# DCDC_Hall.net
KiCad netlist of a schematic drawn in Altium Designer
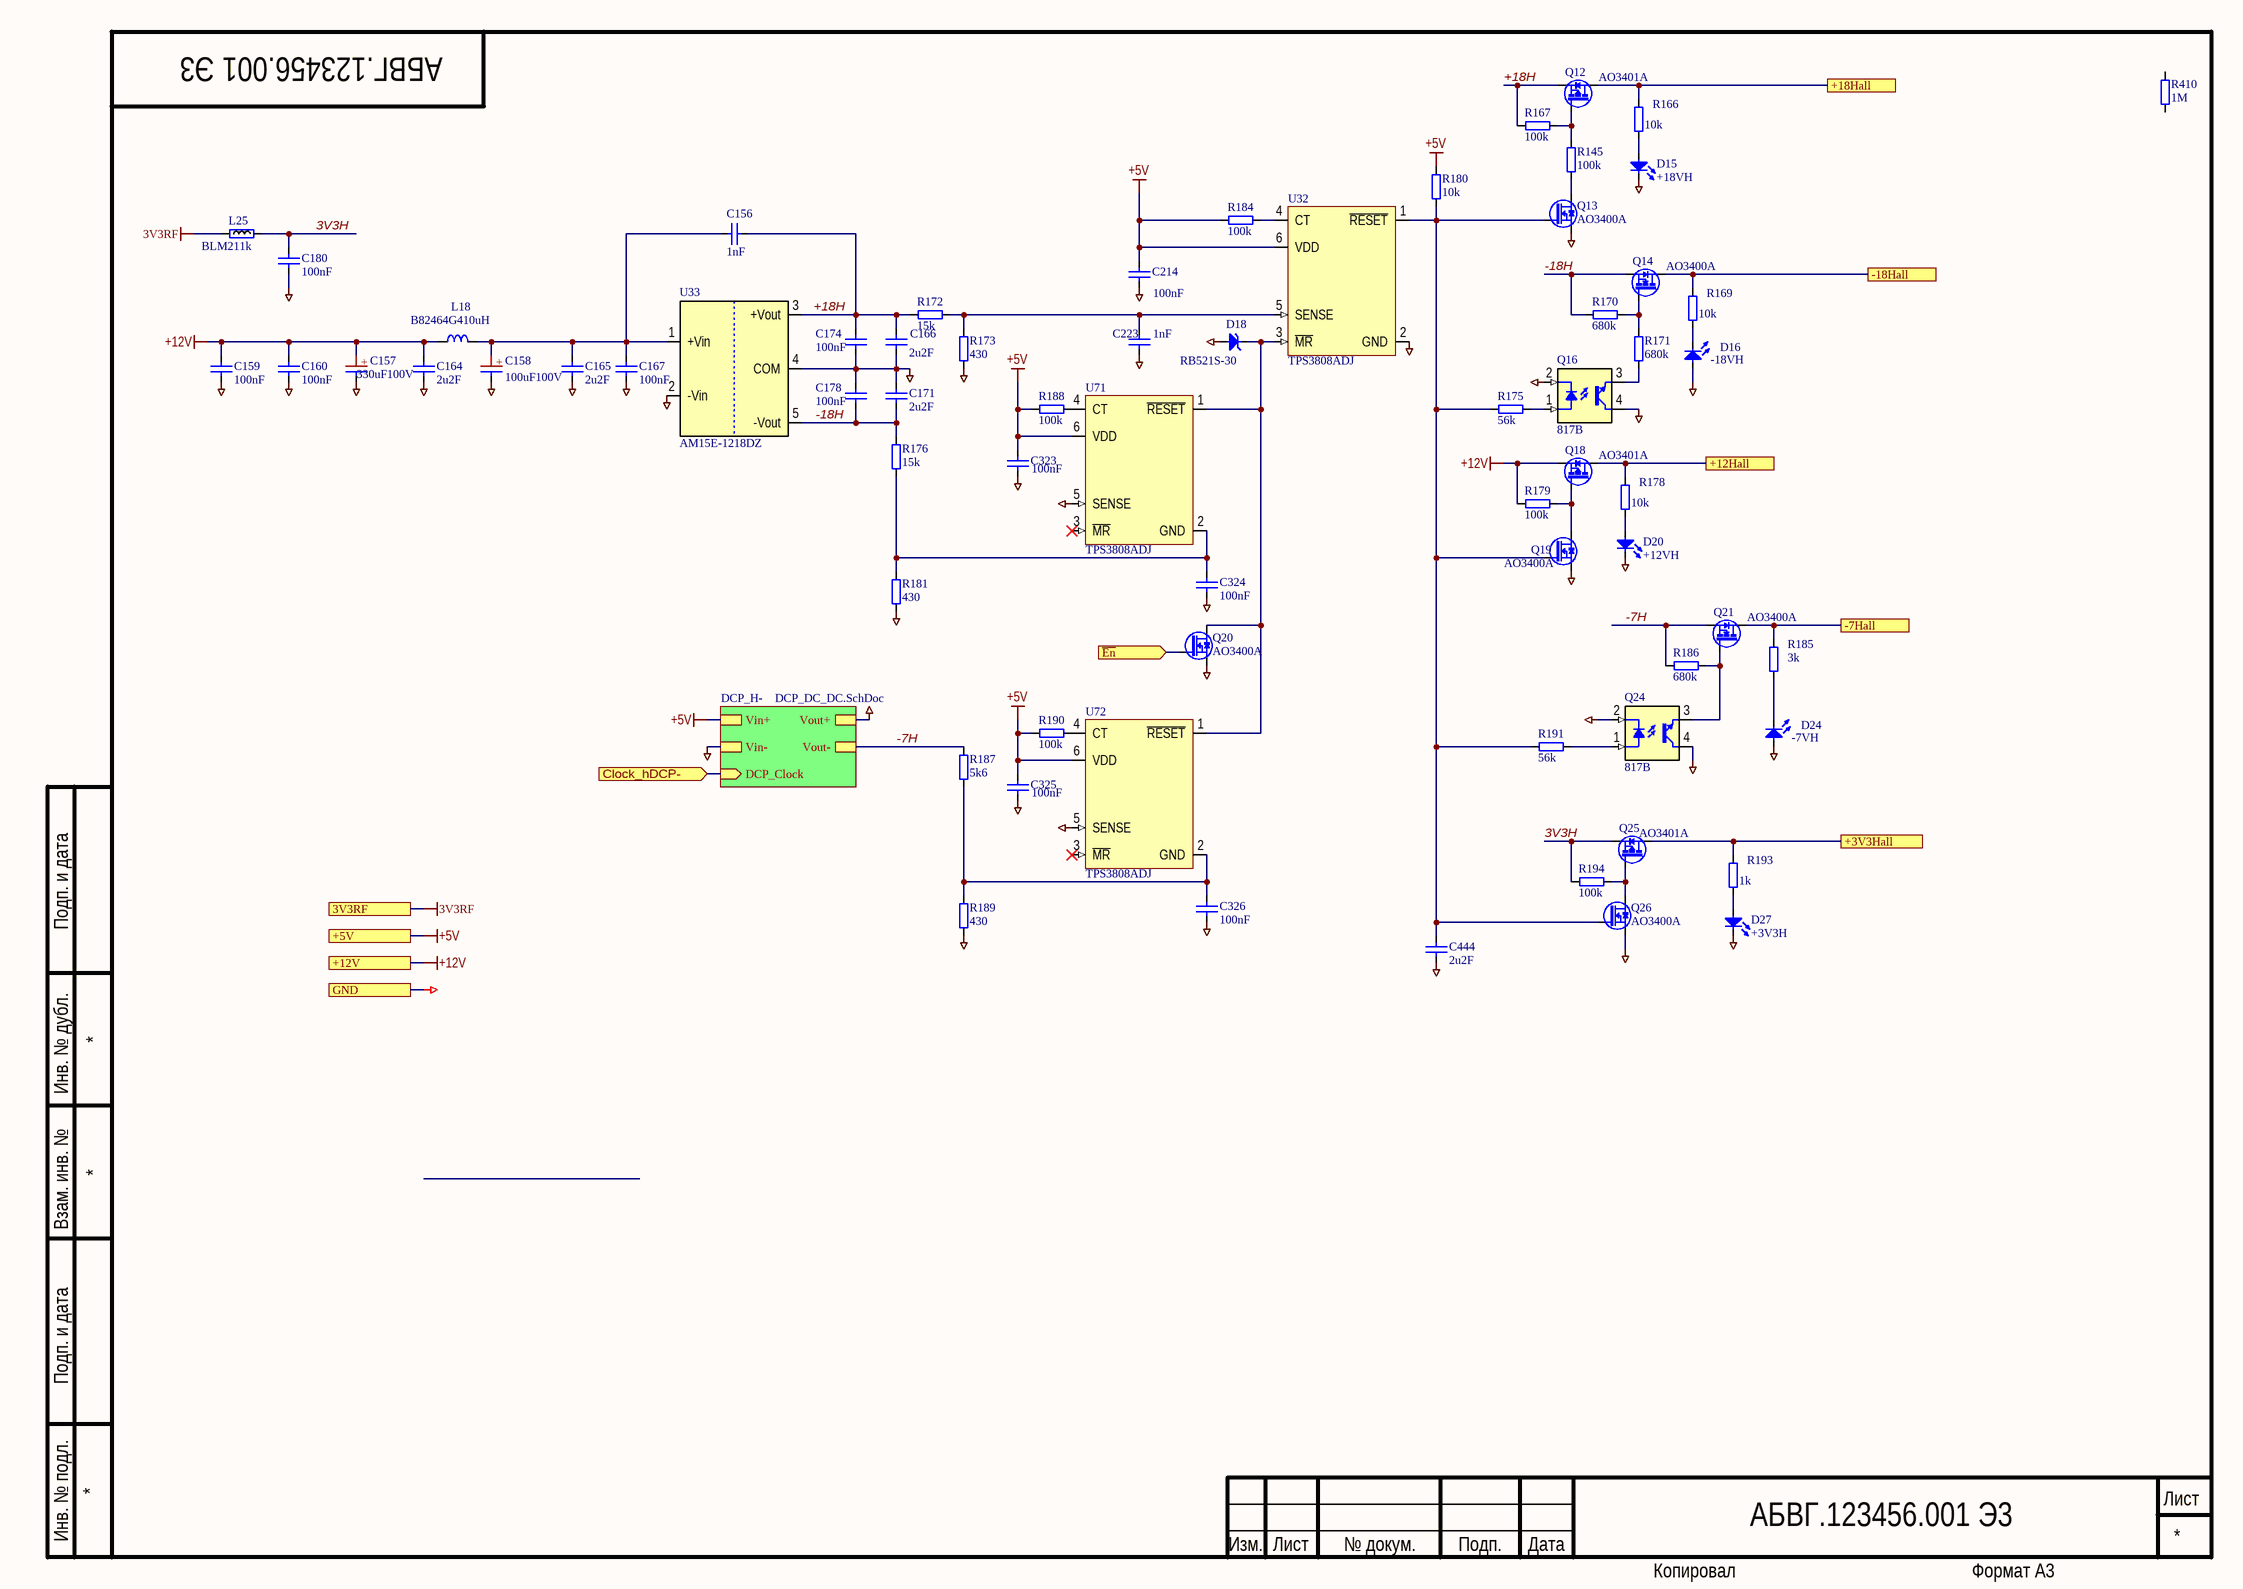
[diagram p0: DCDC_Hall.SchDoc]

(export (version "E")
  (design (tool "Eeschema 10.0.6"))
  (components
    (comp (ref "C156")
      (value "1nF")
      (footprint "SMD0805CAP")
      (description "Чип конденсатор 0805")
      (fields (field (name "VOLTAGE") "25V") (field (name "TOLERANCE") "20%"))
      (libsource (lib "DDSintLib") (part "C0805"))
    )
    (comp (ref "C157")
      (value "330uF100V")
      (footprint "CAPPR750-1600X2000")
      (description "Конденсатор полярный d16 p7.5мм")
      (fields (field (name "VOLTAGE") "100V") (field (name "TOLERANCE") "20%"))
      (libsource (lib "DDSintLib") (part "CAP_POL_7_5x16"))
    )
    (comp (ref "C158")
      (value "100uF100V")
      (footprint "CAPPR500-1000X1250")
      (description "Конденсатор полярный d10 p5мм")
      (fields (field (name "VOLTAGE") "100V") (field (name "TOLERANCE") "20%"))
      (libsource (lib "DDS1") (part "CAP_POL_5x10"))
    )
    (comp (ref "C159")
      (value "100nF")
      (footprint "SMD0805CAP")
      (description "Чип конденсатор 0805")
      (fields (field (name "VOLTAGE") "25V") (field (name "TOLERANCE") "20%"))
      (libsource (lib "DDSintLib") (part "C0805"))
    )
    (comp (ref "C160")
      (value "100nF")
      (footprint "SMD0805CAP")
      (description "Чип конденсатор 0805")
      (fields (field (name "VOLTAGE") "25V") (field (name "TOLERANCE") "20%"))
      (libsource (lib "DDSintLib") (part "C0805"))
    )
    (comp (ref "C164")
      (value "2u2F")
      (footprint "SMD0805CAP")
      (description "Чип конденсатор 0805")
      (fields (field (name "VOLTAGE") "25V") (field (name "TOLERANCE") "20%"))
      (libsource (lib "DDSintLib") (part "C0805"))
    )
    (comp (ref "C165")
      (value "2u2F")
      (footprint "SMD0805CAP")
      (description "Чип конденсатор 0805")
      (fields (field (name "VOLTAGE") "25V") (field (name "TOLERANCE") "20%"))
      (libsource (lib "DDSintLib") (part "C0805"))
    )
    (comp (ref "C166")
      (value "2u2F")
      (footprint "SMD0805CAP")
      (description "Чип конденсатор 0805")
      (fields (field (name "VOLTAGE") "25V") (field (name "TOLERANCE") "20%"))
      (libsource (lib "DDSintLib") (part "C0805"))
    )
    (comp (ref "C167")
      (value "100nF")
      (footprint "SMD0805CAP")
      (description "Чип конденсатор 0805")
      (fields (field (name "VOLTAGE") "25V") (field (name "TOLERANCE") "20%"))
      (libsource (lib "DDSintLib") (part "C0805"))
    )
    (comp (ref "C171")
      (value "2u2F")
      (footprint "SMD0805CAP")
      (description "Чип конденсатор 0805")
      (fields (field (name "VOLTAGE") "25V") (field (name "TOLERANCE") "20%"))
      (libsource (lib "DDSintLib") (part "C0805"))
    )
    (comp (ref "C174")
      (value "100nF")
      (footprint "SMD0805CAP")
      (description "Чип конденсатор 0805")
      (fields (field (name "VOLTAGE") "25V") (field (name "TOLERANCE") "20%"))
      (libsource (lib "DDSintLib") (part "C0805"))
    )
    (comp (ref "C178")
      (value "100nF")
      (footprint "SMD0805CAP")
      (description "Чип конденсатор 0805")
      (fields (field (name "VOLTAGE") "25V") (field (name "TOLERANCE") "20%"))
      (libsource (lib "DDSintLib") (part "C0805"))
    )
    (comp (ref "C180")
      (value "100nF")
      (footprint "SMD0805CAP")
      (description "Чип конденсатор 0805")
      (fields (field (name "VOLTAGE") "25V") (field (name "TOLERANCE") "20%"))
      (libsource (lib "DDSintLib") (part "C0805"))
    )
    (comp (ref "C214")
      (value "100nF")
      (footprint "SMD0805CAP")
      (description "Чип конденсатор 0805")
      (fields (field (name "VOLTAGE") "25V") (field (name "TOLERANCE") "20%"))
      (libsource (lib "DDSintLib") (part "C0805"))
    )
    (comp (ref "C223")
      (value "1nF")
      (footprint "SMD0805CAP")
      (description "Чип конденсатор 0805")
      (fields (field (name "VOLTAGE") "25V") (field (name "TOLERANCE") "20%"))
      (libsource (lib "DDSintLib") (part "C0805"))
    )
    (comp (ref "C323")
      (value "100nF")
      (footprint "SMD0805CAP")
      (description "Чип конденсатор 0805")
      (fields (field (name "VOLTAGE") "25V") (field (name "TOLERANCE") "20%"))
      (libsource (lib "DDSintLib") (part "C0805"))
    )
    (comp (ref "C324")
      (value "100nF")
      (footprint "SMD0805CAP")
      (description "Чип конденсатор 0805")
      (fields (field (name "VOLTAGE") "25V") (field (name "TOLERANCE") "20%"))
      (libsource (lib "DDSintLib") (part "C0805"))
    )
    (comp (ref "C325")
      (value "100nF")
      (footprint "SMD0805CAP")
      (description "Чип конденсатор 0805")
      (fields (field (name "VOLTAGE") "25V") (field (name "TOLERANCE") "20%"))
      (libsource (lib "DDSintLib") (part "C0805"))
    )
    (comp (ref "C326")
      (value "100nF")
      (footprint "SMD0805CAP")
      (description "Чип конденсатор 0805")
      (fields (field (name "VOLTAGE") "25V") (field (name "TOLERANCE") "20%"))
      (libsource (lib "DDSintLib") (part "C0805"))
    )
    (comp (ref "C444")
      (value "2u2F")
      (footprint "SMD0805CAP")
      (description "Чип конденсатор 0805")
      (fields (field (name "VOLTAGE") "25V") (field (name "TOLERANCE") "20%"))
      (libsource (lib "DDSintLib") (part "C0805"))
    )
    (comp (ref "D15")
      (value "+18VH")
      (footprint "LED0603")
      (description "Чип светодиод 0603")
      (libsource (lib "DDSintLib") (part "LED0603"))
    )
    (comp (ref "D16")
      (value "-18VH")
      (footprint "LED0603")
      (description "Чип светодиод 0603")
      (libsource (lib "DDSintLib") (part "LED0603"))
    )
    (comp (ref "D18")
      (value "RB521S-30")
      (footprint "SODFL1608X65N")
      (description "Чип Шоттки диод")
      (fields (field (name "VOLTAGE") "30V"))
      (libsource (lib "DDSintLib") (part "RB521S-30"))
    )
    (comp (ref "D20")
      (value "+12VH")
      (footprint "LED0603")
      (description "Чип светодиод 0603")
      (libsource (lib "DDSintLib") (part "LED0603"))
    )
    (comp (ref "D24")
      (value "-7VH")
      (footprint "LED0603")
      (description "Чип светодиод 0603")
      (libsource (lib "DDSintLib") (part "LED0603"))
    )
    (comp (ref "D27")
      (value "+3V3H")
      (footprint "LED0603")
      (description "Чип светодиод 0603")
      (libsource (lib "DDSintLib") (part "LED0603"))
    )
    (comp (ref "L18")
      (value "B82464G410uH")
      (footprint "IND_COILCRAFT_MSS1038")
      (description "SMD Дроссель")
      (fields (field (name "VOLTAGE") "2") (field (name "TOLERANCE") "20%"))
      (libsource (lib "DDSintLib") (part "B82464G4"))
    )
    (comp (ref "L25")
      (value "BLM211k")
      (footprint "RESC2012X50N")
      (description "SMD Ferrite bead 0805")
      (libsource (lib "DDSintLib") (part "BLM21"))
    )
    (comp (ref "Q12")
      (value "AO3401A")
      (footprint "SOT95P229X119-3N")
      (description "PMOS")
      (fields (field (name "VOLTAGE") "-30V"))
      (libsource (lib "DDSintLib") (part "AO3401A"))
    )
    (comp (ref "Q13")
      (value "AO3400A")
      (footprint "SOT95P229X119-3N")
      (description "NMOS")
      (fields (field (name "VOLTAGE") "30V"))
      (libsource (lib "DDSintLib") (part "AO3400A"))
    )
    (comp (ref "Q14")
      (value "AO3400A")
      (footprint "SOT95P229X119-3N")
      (description "NMOS")
      (fields (field (name "VOLTAGE") "30V"))
      (libsource (lib "DDSintLib") (part "AO3400A"))
    )
    (comp (ref "Q16")
      (value "817B")
      (footprint "DIP4-300")
      (description "Optotransistor")
      (fields (field (name "VOLTAGE") "35V"))
      (libsource (lib "DDS1") (part "817B"))
    )
    (comp (ref "Q18")
      (value "AO3401A")
      (footprint "SOT95P229X119-3N")
      (description "PMOS")
      (fields (field (name "VOLTAGE") "-30V"))
      (libsource (lib "DDSintLib") (part "AO3401A"))
    )
    (comp (ref "Q19")
      (value "AO3400A")
      (footprint "SOT95P229X119-3N")
      (description "NMOS")
      (fields (field (name "VOLTAGE") "30V"))
      (libsource (lib "DDSintLib") (part "AO3400A"))
    )
    (comp (ref "Q20")
      (value "AO3400A")
      (footprint "SOT95P229X119-3N")
      (description "NMOS")
      (fields (field (name "VOLTAGE") "30V"))
      (libsource (lib "DDSintLib") (part "AO3400A"))
    )
    (comp (ref "Q21")
      (value "AO3400A")
      (footprint "SOT95P229X119-3N")
      (description "NMOS")
      (fields (field (name "VOLTAGE") "30V"))
      (libsource (lib "DDSintLib") (part "AO3400A"))
    )
    (comp (ref "Q24")
      (value "817B")
      (footprint "DIP4-300")
      (description "Optotransistor")
      (fields (field (name "VOLTAGE") "35V"))
      (libsource (lib "DDS1") (part "817B"))
    )
    (comp (ref "Q25")
      (value "AO3401A")
      (footprint "SOT95P229X119-3N")
      (description "PMOS")
      (fields (field (name "VOLTAGE") "-30V"))
      (libsource (lib "DDSintLib") (part "AO3401A"))
    )
    (comp (ref "Q26")
      (value "AO3400A")
      (footprint "SOT95P229X119-3N")
      (description "NMOS")
      (fields (field (name "VOLTAGE") "30V"))
      (libsource (lib "DDSintLib") (part "AO3400A"))
    )
    (comp (ref "R145")
      (value "100k")
      (footprint "SMD0805RES")
      (description "Чип резистор 0805")
      (fields (field (name "TOLERANCE") "1%"))
      (libsource (lib "DDSintLib") (part "R0805"))
    )
    (comp (ref "R166")
      (value "10k")
      (footprint "SMD0805RES")
      (description "Чип резистор 0805")
      (fields (field (name "TOLERANCE") "1%"))
      (libsource (lib "DDSintLib") (part "R0805"))
    )
    (comp (ref "R167")
      (value "100k")
      (footprint "SMD0805RES")
      (description "Чип резистор 0805")
      (fields (field (name "TOLERANCE") "1%"))
      (libsource (lib "DDSintLib") (part "R0805"))
    )
    (comp (ref "R169")
      (value "10k")
      (footprint "SMD0805RES")
      (description "Чип резистор 0805")
      (fields (field (name "TOLERANCE") "1%"))
      (libsource (lib "DDSintLib") (part "R0805"))
    )
    (comp (ref "R170")
      (value "680k")
      (footprint "SMD0805RES")
      (description "Чип резистор 0805")
      (fields (field (name "TOLERANCE") "1%"))
      (libsource (lib "DDSintLib") (part "R0805"))
    )
    (comp (ref "R171")
      (value "680k")
      (footprint "SMD0805RES")
      (description "Чип резистор 0805")
      (fields (field (name "TOLERANCE") "1%"))
      (libsource (lib "DDSintLib") (part "R0805"))
    )
    (comp (ref "R172")
      (value "15k")
      (footprint "SMD0805RES")
      (description "Чип резистор 0805")
      (fields (field (name "TOLERANCE") "1%"))
      (libsource (lib "DDSintLib") (part "R0805"))
    )
    (comp (ref "R173")
      (value "430")
      (footprint "SMD0805RES")
      (description "Чип резистор 0805")
      (fields (field (name "TOLERANCE") "1%"))
      (libsource (lib "DDSintLib") (part "R0805"))
    )
    (comp (ref "R175")
      (value "56k")
      (footprint "SMD0805RES")
      (description "Чип резистор 0805")
      (fields (field (name "TOLERANCE") "1%"))
      (libsource (lib "DDSintLib") (part "R0805"))
    )
    (comp (ref "R176")
      (value "15k")
      (footprint "SMD0805RES")
      (description "Чип резистор 0805")
      (fields (field (name "TOLERANCE") "1%"))
      (libsource (lib "DDSintLib") (part "R0805"))
    )
    (comp (ref "R178")
      (value "10k")
      (footprint "SMD0805RES")
      (description "Чип резистор 0805")
      (fields (field (name "TOLERANCE") "1%"))
      (libsource (lib "DDSintLib") (part "R0805"))
    )
    (comp (ref "R179")
      (value "100k")
      (footprint "SMD0805RES")
      (description "Чип резистор 0805")
      (fields (field (name "TOLERANCE") "1%"))
      (libsource (lib "DDSintLib") (part "R0805"))
    )
    (comp (ref "R180")
      (value "10k")
      (footprint "SMD0805RES")
      (description "Чип резистор 0805")
      (fields (field (name "TOLERANCE") "1%"))
      (libsource (lib "DDSintLib") (part "R0805"))
    )
    (comp (ref "R181")
      (value "430")
      (footprint "SMD0805RES")
      (description "Чип резистор 0805")
      (fields (field (name "TOLERANCE") "1%"))
      (libsource (lib "DDSintLib") (part "R0805"))
    )
    (comp (ref "R184")
      (value "100k")
      (footprint "SMD0805RES")
      (description "Чип резистор 0805")
      (fields (field (name "TOLERANCE") "1%"))
      (libsource (lib "DDSintLib") (part "R0805"))
    )
    (comp (ref "R185")
      (value "3k")
      (footprint "SMD0805RES")
      (description "Чип резистор 0805")
      (fields (field (name "TOLERANCE") "1%"))
      (libsource (lib "DDSintLib") (part "R0805"))
    )
    (comp (ref "R186")
      (value "680k")
      (footprint "SMD0805RES")
      (description "Чип резистор 0805")
      (fields (field (name "TOLERANCE") "1%"))
      (libsource (lib "DDSintLib") (part "R0805"))
    )
    (comp (ref "R187")
      (value "5k6")
      (footprint "SMD0805RES")
      (description "Чип резистор 0805")
      (fields (field (name "TOLERANCE") "1%"))
      (libsource (lib "DDSintLib") (part "R0805"))
    )
    (comp (ref "R188")
      (value "100k")
      (footprint "SMD0805RES")
      (description "Чип резистор 0805")
      (fields (field (name "TOLERANCE") "1%"))
      (libsource (lib "DDSintLib") (part "R0805"))
    )
    (comp (ref "R189")
      (value "430")
      (footprint "SMD0805RES")
      (description "Чип резистор 0805")
      (fields (field (name "TOLERANCE") "1%"))
      (libsource (lib "DDSintLib") (part "R0805"))
    )
    (comp (ref "R190")
      (value "100k")
      (footprint "SMD0805RES")
      (description "Чип резистор 0805")
      (fields (field (name "TOLERANCE") "1%"))
      (libsource (lib "DDSintLib") (part "R0805"))
    )
    (comp (ref "R191")
      (value "56k")
      (footprint "SMD0805RES")
      (description "Чип резистор 0805")
      (fields (field (name "TOLERANCE") "1%"))
      (libsource (lib "DDSintLib") (part "R0805"))
    )
    (comp (ref "R193")
      (value "1k")
      (footprint "SMD0805RES")
      (description "Чип резистор 0805")
      (fields (field (name "TOLERANCE") "1%"))
      (libsource (lib "DDSintLib") (part "R0805"))
    )
    (comp (ref "R194")
      (value "100k")
      (footprint "SMD0805RES")
      (description "Чип резистор 0805")
      (fields (field (name "TOLERANCE") "1%"))
      (libsource (lib "DDSintLib") (part "R0805"))
    )
    (comp (ref "R410")
      (value "1M")
      (footprint "SMD0805RES")
      (description "Чип резистор 0805")
      (fields (field (name "TOLERANCE") "1%"))
      (libsource (lib "DDSintLib") (part "R0805"))
    )
    (comp (ref "U32")
      (value "TPS3808ADJ")
      (footprint "SOT95P270X145-6N")
      (description "Supervisory Circuit. Low-Quiescent-Current, Programmable-Delay")
      (libsource (lib "DDS1") (part "TPS3808"))
    )
    (comp (ref "U33")
      (value "AM15E-1218DZ")
      (footprint "AM15E")
      (description "Negative LDO Linear stabilizer")
      (libsource (lib "DDS1") (part "AM15E-"))
    )
    (comp (ref "U71")
      (value "TPS3808ADJ")
      (footprint "SOT95P270X145-6N")
      (description "Supervisory Circuit. Low-Quiescent-Current, Programmable-Delay")
      (libsource (lib "DDS1") (part "TPS3808"))
    )
    (comp (ref "U72")
      (value "TPS3808ADJ")
      (footprint "SOT95P270X145-6N")
      (description "Supervisory Circuit. Low-Quiescent-Current, Programmable-Delay")
      (libsource (lib "DDS1") (part "TPS3808"))
    )
  )
  (nets
    (net (code "1") (name "+5V") (class "Default")
      (node (ref "C214") (pin "2") (pinfunction "2_2") (pintype "passive"))
      (node (ref "C323") (pin "2") (pinfunction "2_2") (pintype "passive"))
      (node (ref "C325") (pin "2") (pinfunction "2_2") (pintype "passive"))
      (node (ref "R180") (pin "1") (pinfunction "1_1") (pintype "passive"))
      (node (ref "R184") (pin "1") (pinfunction "1_1") (pintype "passive"))
      (node (ref "R188") (pin "1") (pinfunction "1_1") (pintype "passive"))
      (node (ref "R190") (pin "1") (pinfunction "1_1") (pintype "passive"))
      (node (ref "U32") (pin "6") (pinfunction "VDD_6") (pintype "power_in"))
      (node (ref "U71") (pin "6") (pinfunction "VDD_6") (pintype "power_in"))
      (node (ref "U72") (pin "6") (pinfunction "VDD_6") (pintype "power_in"))
    )
    (net (code "2") (name "+12V") (class "Default")
      (node (ref "C157") (pin "1") (pinfunction "+_1") (pintype "passive"))
      (node (ref "C159") (pin "2") (pinfunction "2_2") (pintype "passive"))
      (node (ref "C160") (pin "2") (pinfunction "2_2") (pintype "passive"))
      (node (ref "C164") (pin "2") (pinfunction "2_2") (pintype "passive"))
      (node (ref "L18") (pin "1") (pinfunction "1_1") (pintype "passive"))
      (node (ref "Q18") (pin "2") (pinfunction "S_2") (pintype "passive"))
      (node (ref "R179") (pin "2") (pinfunction "2_2") (pintype "passive"))
    )
    (net (code "3") (name "/+3V3Hall") (class "Default")
      (node (ref "Q25") (pin "3") (pinfunction "D_3") (pintype "passive"))
      (node (ref "R193") (pin "2") (pinfunction "2_2") (pintype "passive"))
    )
    (net (code "4") (name "/+12Hall") (class "Default")
      (node (ref "Q18") (pin "3") (pinfunction "D_3") (pintype "passive"))
      (node (ref "R178") (pin "2") (pinfunction "2_2") (pintype "passive"))
    )
    (net (code "5") (name "/+18H") (class "Default")
      (node (ref "C156") (pin "2") (pinfunction "2_2") (pintype "passive"))
      (node (ref "C166") (pin "2") (pinfunction "2_2") (pintype "passive"))
      (node (ref "C174") (pin "1") (pinfunction "1_1") (pintype "passive"))
      (node (ref "Q12") (pin "2") (pinfunction "S_2") (pintype "passive"))
      (node (ref "R167") (pin "2") (pinfunction "2_2") (pintype "passive"))
      (node (ref "R172") (pin "2") (pinfunction "2_2") (pintype "passive"))
      (node (ref "U33") (pin "3") (pinfunction "+Vout_3") (pintype "power_in"))
    )
    (net (code "6") (name "/+18Hall") (class "Default")
      (node (ref "Q12") (pin "3") (pinfunction "D_3") (pintype "passive"))
      (node (ref "R166") (pin "2") (pinfunction "2_2") (pintype "passive"))
    )
    (net (code "7") (name "/-7H") (class "Default")
      (node (ref "Q21") (pin "2") (pinfunction "S_2") (pintype "passive"))
      (node (ref "R186") (pin "2") (pinfunction "2_2") (pintype "passive"))
      (node (ref "R187") (pin "1") (pinfunction "1_1") (pintype "passive"))
    )
    (net (code "8") (name "/-7Hall") (class "Default")
      (node (ref "Q21") (pin "3") (pinfunction "D_3") (pintype "passive"))
      (node (ref "R185") (pin "2") (pinfunction "2_2") (pintype "passive"))
    )
    (net (code "9") (name "/-18H") (class "Default")
      (node (ref "C171") (pin "1") (pinfunction "1_1") (pintype "passive"))
      (node (ref "C178") (pin "2") (pinfunction "2_2") (pintype "passive"))
      (node (ref "Q14") (pin "2") (pinfunction "S_2") (pintype "passive"))
      (node (ref "R170") (pin "2") (pinfunction "2_2") (pintype "passive"))
      (node (ref "R176") (pin "1") (pinfunction "1_1") (pintype "passive"))
      (node (ref "U33") (pin "5") (pinfunction "-Vout_5") (pintype "power_in"))
    )
    (net (code "10") (name "/-18Hall") (class "Default")
      (node (ref "Q14") (pin "3") (pinfunction "D_3") (pintype "passive"))
      (node (ref "R169") (pin "2") (pinfunction "2_2") (pintype "passive"))
    )
    (net (code "11") (name "/3V3H") (class "Default")
      (node (ref "C180") (pin "2") (pinfunction "2_2") (pintype "passive"))
      (node (ref "L25") (pin "1") (pinfunction "1_1") (pintype "passive"))
      (node (ref "Q25") (pin "2") (pinfunction "S_2") (pintype "passive"))
      (node (ref "R194") (pin "2") (pinfunction "2_2") (pintype "passive"))
    )
    (net (code "13") (name "/En") (class "Default")
      (node (ref "Q20") (pin "1") (pinfunction "G_1") (pintype "passive"))
    )
    (net (code "14") (name "3V3RF") (class "Default")
      (node (ref "L25") (pin "2") (pinfunction "2_2") (pintype "passive"))
    )
    (net (code "15") (name "GND") (class "Default")
      (node (ref "C157") (pin "2") (pinfunction "2_2") (pintype "passive"))
      (node (ref "C158") (pin "2") (pinfunction "2_2") (pintype "passive"))
      (node (ref "C159") (pin "1") (pinfunction "1_1") (pintype "passive"))
      (node (ref "C160") (pin "1") (pinfunction "1_1") (pintype "passive"))
      (node (ref "C164") (pin "1") (pinfunction "1_1") (pintype "passive"))
      (node (ref "C165") (pin "1") (pinfunction "1_1") (pintype "passive"))
      (node (ref "C166") (pin "1") (pinfunction "1_1") (pintype "passive"))
      (node (ref "C167") (pin "2") (pinfunction "2_2") (pintype "passive"))
      (node (ref "C171") (pin "2") (pinfunction "2_2") (pintype "passive"))
      (node (ref "C174") (pin "2") (pinfunction "2_2") (pintype "passive"))
      (node (ref "C178") (pin "1") (pinfunction "1_1") (pintype "passive"))
      (node (ref "C180") (pin "1") (pinfunction "1_1") (pintype "passive"))
      (node (ref "C214") (pin "1") (pinfunction "1_1") (pintype "passive"))
      (node (ref "C223") (pin "1") (pinfunction "1_1") (pintype "passive"))
      (node (ref "C323") (pin "1") (pinfunction "1_1") (pintype "passive"))
      (node (ref "C324") (pin "2") (pinfunction "2_2") (pintype "passive"))
      (node (ref "C325") (pin "1") (pinfunction "1_1") (pintype "passive"))
      (node (ref "C326") (pin "2") (pinfunction "2_2") (pintype "passive"))
      (node (ref "C444") (pin "2") (pinfunction "2_2") (pintype "passive"))
      (node (ref "D15") (pin "1") (pinfunction "C_1") (pintype "passive"))
      (node (ref "D16") (pin "2") (pinfunction "A_2") (pintype "passive"))
      (node (ref "D18") (pin "2") (pinfunction "A_2") (pintype "passive"))
      (node (ref "D20") (pin "1") (pinfunction "C_1") (pintype "passive"))
      (node (ref "D24") (pin "2") (pinfunction "A_2") (pintype "passive"))
      (node (ref "D27") (pin "1") (pinfunction "C_1") (pintype "passive"))
      (node (ref "Q13") (pin "2") (pinfunction "S_2") (pintype "passive"))
      (node (ref "Q16") (pin "2") (pinfunction "C_2") (pintype "input"))
      (node (ref "Q16") (pin "4") (pinfunction "C_4") (pintype "open_collector"))
      (node (ref "Q19") (pin "2") (pinfunction "S_2") (pintype "passive"))
      (node (ref "Q20") (pin "2") (pinfunction "S_2") (pintype "passive"))
      (node (ref "Q24") (pin "2") (pinfunction "C_2") (pintype "input"))
      (node (ref "Q24") (pin "4") (pinfunction "C_4") (pintype "open_collector"))
      (node (ref "Q26") (pin "2") (pinfunction "S_2") (pintype "passive"))
      (node (ref "R173") (pin "1") (pinfunction "1_1") (pintype "passive"))
      (node (ref "R181") (pin "1") (pinfunction "1_1") (pintype "passive"))
      (node (ref "R189") (pin "1") (pinfunction "1_1") (pintype "passive"))
      (node (ref "U32") (pin "2") (pinfunction "GND_2") (pintype "power_in"))
      (node (ref "U33") (pin "2") (pinfunction "-Vin_2") (pintype "power_in"))
      (node (ref "U33") (pin "4") (pinfunction "COM_4") (pintype "power_in"))
      (node (ref "U71") (pin "5") (pinfunction "SENSE_5") (pintype "input"))
      (node (ref "U72") (pin "5") (pinfunction "SENSE_5") (pintype "input"))
    )
    (net (code "16") (name "Net-(C158-+)") (class "Default")
      (node (ref "C156") (pin "1") (pinfunction "1_1") (pintype "passive"))
      (node (ref "C158") (pin "1") (pinfunction "+_1") (pintype "passive"))
      (node (ref "C165") (pin "2") (pinfunction "2_2") (pintype "passive"))
      (node (ref "C167") (pin "1") (pinfunction "1_1") (pintype "passive"))
      (node (ref "L18") (pin "2") (pinfunction "2_2") (pintype "passive"))
      (node (ref "U33") (pin "1") (pinfunction "+Vin_1") (pintype "power_in"))
    )
    (net (code "17") (name "Net-(D15-A)") (class "Default")
      (node (ref "D15") (pin "2") (pinfunction "A_2") (pintype "passive"))
      (node (ref "R166") (pin "1") (pinfunction "1_1") (pintype "passive"))
    )
    (net (code "18") (name "Net-(D16-C)") (class "Default")
      (node (ref "D16") (pin "1") (pinfunction "C_1") (pintype "passive"))
      (node (ref "R169") (pin "1") (pinfunction "1_1") (pintype "passive"))
    )
    (net (code "19") (name "Net-(D18-C)") (class "Default")
      (node (ref "D18") (pin "1") (pinfunction "C_1") (pintype "passive"))
      (node (ref "Q20") (pin "3") (pinfunction "D_3") (pintype "passive"))
      (node (ref "U32") (pin "3") (pinfunction "~{MR}_3") (pintype "input"))
      (node (ref "U71") (pin "1") (pinfunction "~{RESET}_1") (pintype "open_collector"))
      (node (ref "U72") (pin "1") (pinfunction "~{RESET}_1") (pintype "open_collector"))
    )
    (net (code "20") (name "Net-(D20-A)") (class "Default")
      (node (ref "D20") (pin "2") (pinfunction "A_2") (pintype "passive"))
      (node (ref "R178") (pin "1") (pinfunction "1_1") (pintype "passive"))
    )
    (net (code "21") (name "Net-(D24-C)") (class "Default")
      (node (ref "D24") (pin "1") (pinfunction "C_1") (pintype "passive"))
      (node (ref "R185") (pin "1") (pinfunction "1_1") (pintype "passive"))
    )
    (net (code "22") (name "Net-(D27-A)") (class "Default")
      (node (ref "D27") (pin "2") (pinfunction "A_2") (pintype "passive"))
      (node (ref "R193") (pin "1") (pinfunction "1_1") (pintype "passive"))
    )
    (net (code "23") (name "Net-(Q12-G)") (class "Default")
      (node (ref "Q12") (pin "1") (pinfunction "G_1") (pintype "passive"))
      (node (ref "R145") (pin "2") (pinfunction "2_2") (pintype "passive"))
      (node (ref "R167") (pin "1") (pinfunction "1_1") (pintype "passive"))
    )
    (net (code "24") (name "Net-(Q13-D)") (class "Default")
      (node (ref "Q13") (pin "3") (pinfunction "D_3") (pintype "passive"))
      (node (ref "R145") (pin "1") (pinfunction "1_1") (pintype "passive"))
    )
    (net (code "25") (name "Net-(Q13-G)") (class "Default")
      (node (ref "C444") (pin "1") (pinfunction "1_1") (pintype "passive"))
      (node (ref "Q13") (pin "1") (pinfunction "G_1") (pintype "passive"))
      (node (ref "Q19") (pin "1") (pinfunction "G_1") (pintype "passive"))
      (node (ref "Q26") (pin "1") (pinfunction "G_1") (pintype "passive"))
      (node (ref "R175") (pin "1") (pinfunction "1_1") (pintype "passive"))
      (node (ref "R180") (pin "2") (pinfunction "2_2") (pintype "passive"))
      (node (ref "R191") (pin "1") (pinfunction "1_1") (pintype "passive"))
      (node (ref "U32") (pin "1") (pinfunction "~{RESET}_1") (pintype "open_collector"))
    )
    (net (code "26") (name "Net-(Q14-G)") (class "Default")
      (node (ref "Q14") (pin "1") (pinfunction "G_1") (pintype "passive"))
      (node (ref "R170") (pin "1") (pinfunction "1_1") (pintype "passive"))
      (node (ref "R171") (pin "2") (pinfunction "2_2") (pintype "passive"))
    )
    (net (code "27") (name "Net-(Q16-A)") (class "Default")
      (node (ref "Q16") (pin "1") (pinfunction "A_1") (pintype "input"))
      (node (ref "R175") (pin "2") (pinfunction "2_2") (pintype "passive"))
    )
    (net (code "28") (name "Net-(Q16-E)") (class "Default")
      (node (ref "Q16") (pin "3") (pinfunction "E_3") (pintype "open_emitter"))
      (node (ref "R171") (pin "1") (pinfunction "1_1") (pintype "passive"))
    )
    (net (code "29") (name "Net-(Q18-G)") (class "Default")
      (node (ref "Q18") (pin "1") (pinfunction "G_1") (pintype "passive"))
      (node (ref "Q19") (pin "3") (pinfunction "D_3") (pintype "passive"))
      (node (ref "R179") (pin "1") (pinfunction "1_1") (pintype "passive"))
    )
    (net (code "30") (name "Net-(Q21-G)") (class "Default")
      (node (ref "Q21") (pin "1") (pinfunction "G_1") (pintype "passive"))
      (node (ref "Q24") (pin "3") (pinfunction "E_3") (pintype "open_emitter"))
      (node (ref "R186") (pin "1") (pinfunction "1_1") (pintype "passive"))
    )
    (net (code "31") (name "Net-(Q24-A)") (class "Default")
      (node (ref "Q24") (pin "1") (pinfunction "A_1") (pintype "input"))
      (node (ref "R191") (pin "2") (pinfunction "2_2") (pintype "passive"))
    )
    (net (code "32") (name "Net-(Q25-G)") (class "Default")
      (node (ref "Q25") (pin "1") (pinfunction "G_1") (pintype "passive"))
      (node (ref "Q26") (pin "3") (pinfunction "D_3") (pintype "passive"))
      (node (ref "R194") (pin "1") (pinfunction "1_1") (pintype "passive"))
    )
    (net (code "33") (name "Net-(U32-CT)") (class "Default")
      (node (ref "R184") (pin "2") (pinfunction "2_2") (pintype "passive"))
      (node (ref "U32") (pin "4") (pinfunction "CT_4") (pintype "passive"))
    )
    (net (code "34") (name "Net-(U32-SENSE)") (class "Default")
      (node (ref "C223") (pin "2") (pinfunction "2_2") (pintype "passive"))
      (node (ref "R172") (pin "1") (pinfunction "1_1") (pintype "passive"))
      (node (ref "R173") (pin "2") (pinfunction "2_2") (pintype "passive"))
      (node (ref "U32") (pin "5") (pinfunction "SENSE_5") (pintype "input"))
    )
    (net (code "35") (name "Net-(U71-CT)") (class "Default")
      (node (ref "R188") (pin "2") (pinfunction "2_2") (pintype "passive"))
      (node (ref "U71") (pin "4") (pinfunction "CT_4") (pintype "passive"))
    )
    (net (code "36") (name "Net-(U71-GND)") (class "Default")
      (node (ref "C324") (pin "1") (pinfunction "1_1") (pintype "passive"))
      (node (ref "R176") (pin "2") (pinfunction "2_2") (pintype "passive"))
      (node (ref "R181") (pin "2") (pinfunction "2_2") (pintype "passive"))
      (node (ref "U71") (pin "2") (pinfunction "GND_2") (pintype "power_in"))
    )
    (net (code "37") (name "Net-(U72-CT)") (class "Default")
      (node (ref "R190") (pin "2") (pinfunction "2_2") (pintype "passive"))
      (node (ref "U72") (pin "4") (pinfunction "CT_4") (pintype "passive"))
    )
    (net (code "38") (name "Net-(U72-GND)") (class "Default")
      (node (ref "C326") (pin "1") (pinfunction "1_1") (pintype "passive"))
      (node (ref "R187") (pin "2") (pinfunction "2_2") (pintype "passive"))
      (node (ref "R189") (pin "2") (pinfunction "2_2") (pintype "passive"))
      (node (ref "U72") (pin "2") (pinfunction "GND_2") (pintype "power_in"))
    )
    (net (code "39") (name "unconnected-(R410-Pad1)") (class "Default")
      (node (ref "R410") (pin "1") (pinfunction "1_1") (pintype "passive"))
    )
    (net (code "40") (name "unconnected-(R410-Pad2)") (class "Default")
      (node (ref "R410") (pin "2") (pinfunction "2_2") (pintype "passive"))
    )
    (net (code "41") (name "unconnected-(U71-~{MR}-Pad3)") (class "Default")
      (node (ref "U71") (pin "3") (pinfunction "~{MR}_3") (pintype "input+no_connect"))
    )
    (net (code "42") (name "unconnected-(U72-~{MR}-Pad3)") (class "Default")
      (node (ref "U72") (pin "3") (pinfunction "~{MR}_3") (pintype "input+no_connect"))
    )
  )
)
